# SparkFun_u-blox_GNSS_MAX-M10S.net
KiCad netlist of a schematic drawn in EAGLE
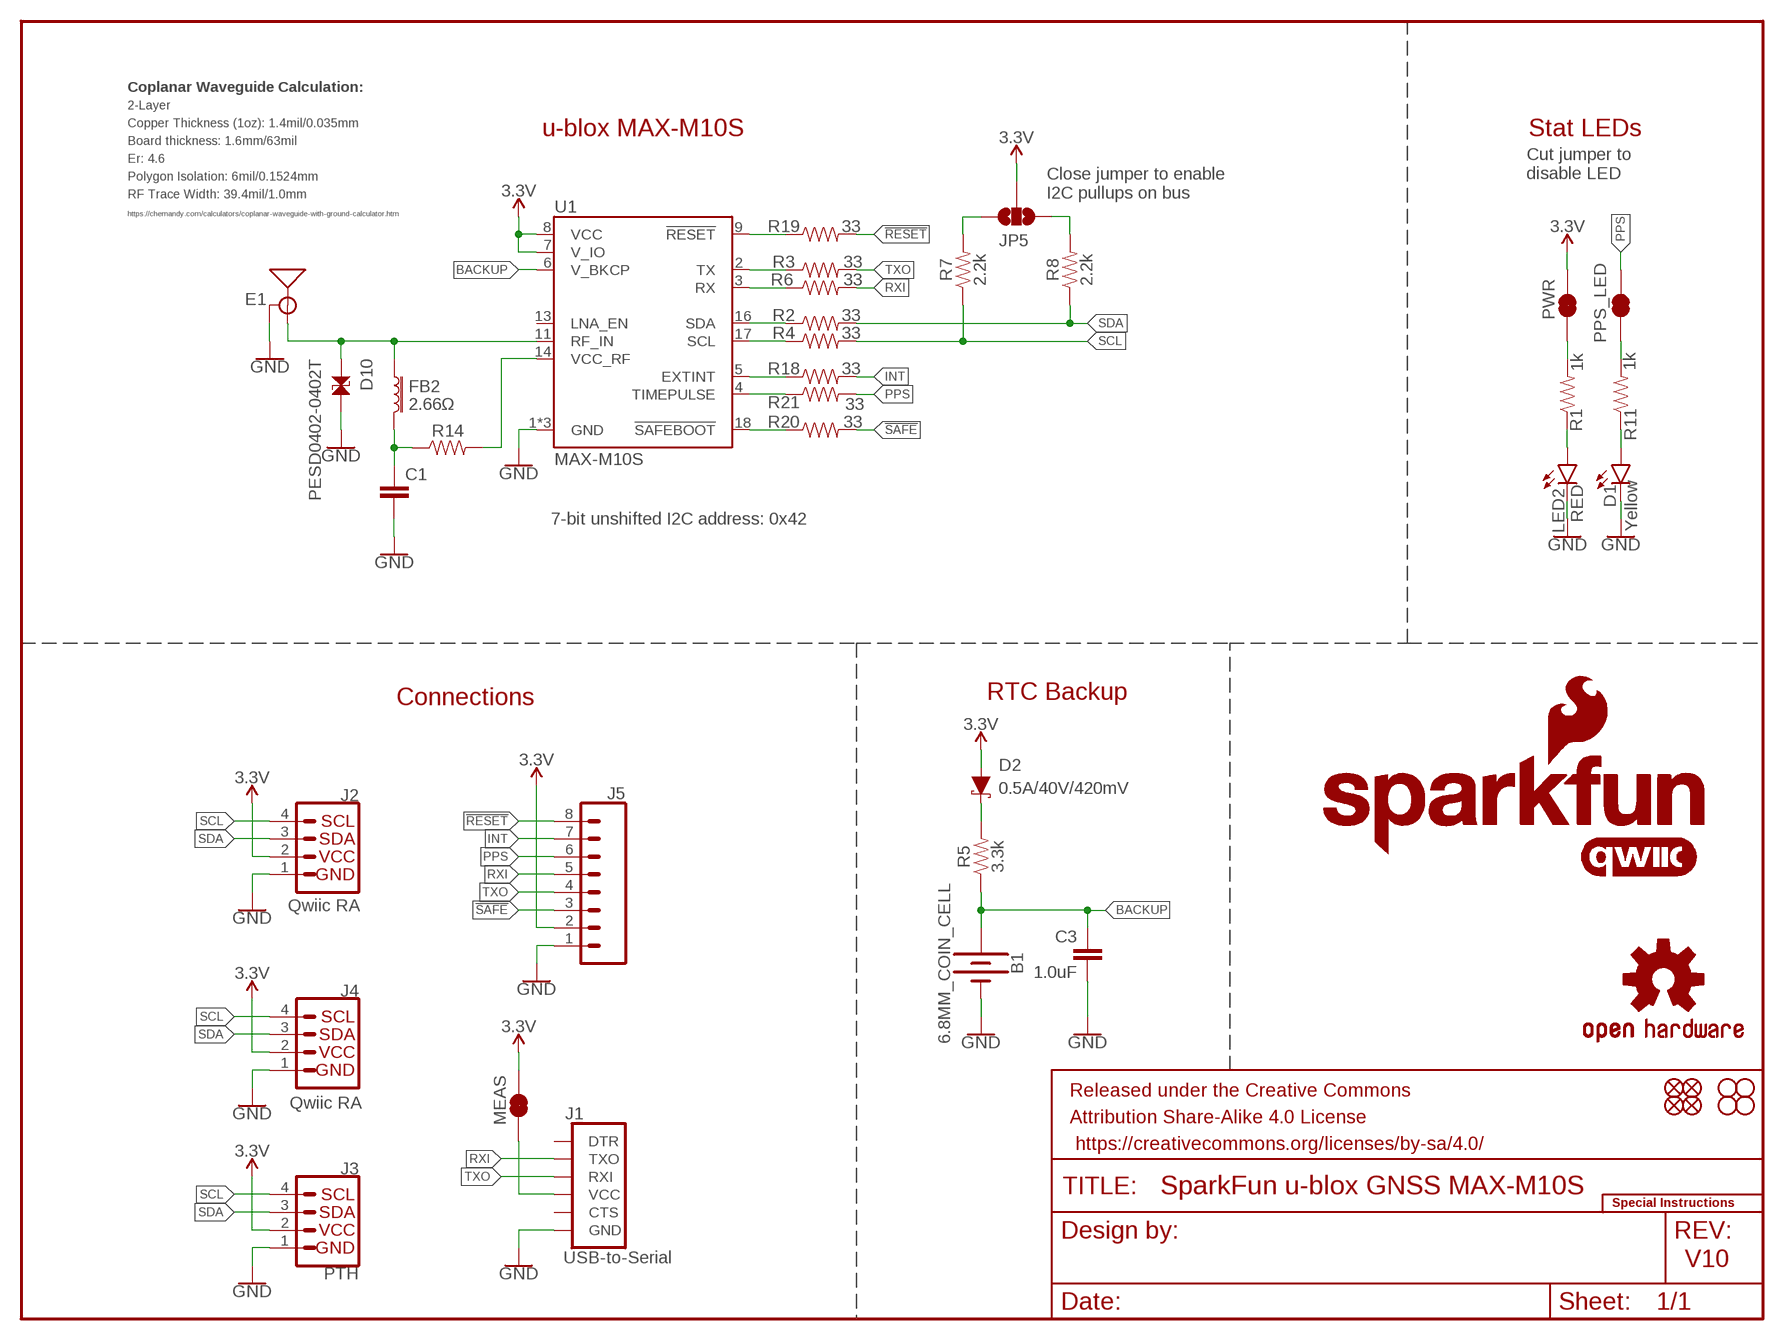
[diagram p0: schematic, sheet 1]

(export (version "E")
  (design (tool "Eeschema 10.0.6"))
  (components
    (comp (ref "B1")
      (value "6.8MM_COIN_CELL")
      (footprint "eagle-import:ML414H_IV01E")
      (libsource (lib "eagle-import") (part "ML414H_IV01E_BATTERY"))
    )
    (comp (ref "C1")
      (value "47pF")
      (footprint "eagle-import:0402-TIGHT")
      (libsource (lib "eagle-import") (part "47PF-0402_TIGHT-25V-5%-X7R"))
    )
    (comp (ref "C3")
      (value "1.0uF")
      (footprint "eagle-import:0603")
      (libsource (lib "eagle-import") (part "1.0UF-0603-16V-10%-X7R"))
    )
    (comp (ref "D1")
      (value "Yellow")
      (footprint "eagle-import:LED-0603")
      (libsource (lib "eagle-import") (part "LED-YELLOW0603"))
    )
    (comp (ref "D2")
      (value "0.5A/40V/420mV")
      (footprint "eagle-import:SOD-323")
      (libsource (lib "eagle-import") (part "DIODE-SCHOTTKY-PMEG4005EJ"))
    )
    (comp (ref "D10")
      (value "PESD0402-0402T")
      (footprint "eagle-import:0402-TIGHT")
      (libsource (lib "eagle-import") (part "PESD0402-0402T"))
    )
    (comp (ref "E1")
      (value "ANTENNA-SMA-GROUNDEDEDGE_SMA")
      (footprint "eagle-import:SMA-EDGE")
      (libsource (lib "eagle-import") (part "ANTENNA-SMA-GROUNDEDEDGE_SMA"))
    )
    (comp (ref "FB2")
      (value "2.66Ω")
      (footprint "eagle-import:0402-TIGHT")
      (libsource (lib "eagle-import") (part "FERRITE_BEAD-0402-2.66Ω-1GHZ"))
    )
    (comp (ref "FD1")
      (value "FIDUCIALUFIDUCIAL")
      (footprint "eagle-import:FIDUCIAL-MICRO")
      (libsource (lib "eagle-import") (part "FIDUCIALUFIDUCIAL"))
    )
    (comp (ref "FD2")
      (value "FIDUCIALUFIDUCIAL")
      (footprint "eagle-import:FIDUCIAL-MICRO")
      (libsource (lib "eagle-import") (part "FIDUCIALUFIDUCIAL"))
    )
    (comp (ref "FD3")
      (value "FIDUCIALUFIDUCIAL")
      (footprint "eagle-import:FIDUCIAL-MICRO")
      (libsource (lib "eagle-import") (part "FIDUCIALUFIDUCIAL"))
    )
    (comp (ref "FD4")
      (value "FIDUCIALUFIDUCIAL")
      (footprint "eagle-import:FIDUCIAL-MICRO")
      (libsource (lib "eagle-import") (part "FIDUCIALUFIDUCIAL"))
    )
    (comp (ref "FRAME1")
      (value "FRAME-LETTER")
      (footprint "eagle-import:CREATIVE_COMMONS")
      (libsource (lib "eagle-import") (part "FRAME-LETTER"))
    )
    (comp (ref "H1")
      (value "STAND-OFF")
      (footprint "eagle-import:STAND-OFF")
      (libsource (lib "eagle-import") (part "STAND-OFF"))
    )
    (comp (ref "H2")
      (value "STAND-OFF")
      (footprint "eagle-import:STAND-OFF")
      (libsource (lib "eagle-import") (part "STAND-OFF"))
    )
    (comp (ref "H3")
      (value "STAND-OFF")
      (footprint "eagle-import:STAND-OFF")
      (libsource (lib "eagle-import") (part "STAND-OFF"))
    )
    (comp (ref "H4")
      (value "STAND-OFF")
      (footprint "eagle-import:STAND-OFF")
      (libsource (lib "eagle-import") (part "STAND-OFF"))
    )
    (comp (ref "J1")
      (value "USB-to-Serial")
      (footprint "eagle-import:1X06_NO_SILK")
      (libsource (lib "eagle-import") (part "6_PIN_SERIAL_TARGET_NO_SILK"))
    )
    (comp (ref "J2")
      (value "Qwiic RA")
      (footprint "eagle-import:JST04_1MM_RA")
      (libsource (lib "eagle-import") (part "I2C_STANDARDQWIIC"))
    )
    (comp (ref "J3")
      (value "PTH")
      (footprint "eagle-import:1X04_NO_SILK")
      (libsource (lib "eagle-import") (part "SparkX_I2C_STANDARD_NO_SILK"))
    )
    (comp (ref "J4")
      (value "Qwiic RA")
      (footprint "eagle-import:JST04_1MM_RA")
      (libsource (lib "eagle-import") (part "I2C_STANDARDQWIIC"))
    )
    (comp (ref "J5")
      (value "CONN_08NO_SILK_DNP")
      (footprint "eagle-import:1X08_NO_SILK")
      (libsource (lib "eagle-import") (part "CONN_08NO_SILK_DNP"))
    )
    (comp (ref "JP5")
      (value "JUMPER-SMT_3_NO_SILK")
      (footprint "eagle-import:SMT-JUMPER_3_NO_SILK")
      (libsource (lib "eagle-import") (part "JUMPER-SMT_3_NO_SILK"))
    )
    (comp (ref "LED2")
      (value "RED")
      (footprint "eagle-import:LED-0603")
      (libsource (lib "eagle-import") (part "LED-RED0603"))
    )
    (comp (ref "LOGO1")
      (value "OSHW-LOGOMINI")
      (footprint "eagle-import:OSHW-LOGO-MINI")
      (libsource (lib "eagle-import") (part "OSHW-LOGOMINI"))
    )
    (comp (ref "LOGO2")
      (value "SFE_LOGO_NAME_FLAME.1_INCH")
      (footprint "eagle-import:SFE_LOGO_NAME_FLAME_.1")
      (libsource (lib "eagle-import") (part "SFE_LOGO_NAME_FLAME.1_INCH"))
    )
    (comp (ref "LOGO3")
      (value "QWIIC_LOGO_5MM")
      (footprint "eagle-import:QWIIC_5MM")
      (libsource (lib "eagle-import") (part "QWIIC_LOGO_5MM"))
    )
    (comp (ref "LOGO4")
      (value "SFE_LOGO_NAME.1_INCH")
      (footprint "eagle-import:SFE_LOGO_NAME_.1")
      (libsource (lib "eagle-import") (part "SFE_LOGO_NAME.1_INCH"))
    )
    (comp (ref "MEAS")
      (value "JUMPER-COMBO_2_NC_TRACE")
      (footprint "eagle-import:COMBO-JUMPER_2_NC_TRACE")
      (libsource (lib "eagle-import") (part "JUMPER-COMBO_2_NC_TRACE"))
    )
    (comp (ref "PPS_LED")
      (value "JUMPER-SMT_2_NC_TRACE_SILK")
      (footprint "eagle-import:SMT-JUMPER_2_NC_TRACE_SILK")
      (libsource (lib "eagle-import") (part "JUMPER-SMT_2_NC_TRACE_SILK"))
    )
    (comp (ref "PWR")
      (value "JUMPER-SMT_2_NC_TRACE_SILK")
      (footprint "eagle-import:SMT-JUMPER_2_NC_TRACE_SILK")
      (libsource (lib "eagle-import") (part "JUMPER-SMT_2_NC_TRACE_SILK"))
    )
    (comp (ref "R1")
      (value "1k")
      (footprint "eagle-import:0603")
      (libsource (lib "eagle-import") (part "1KOHM-0603-1/10W-1%"))
    )
    (comp (ref "R2")
      (value "33")
      (footprint "eagle-import:0603")
      (libsource (lib "eagle-import") (part "33OHM-0603-1/10W-1%"))
    )
    (comp (ref "R3")
      (value "33")
      (footprint "eagle-import:0603")
      (libsource (lib "eagle-import") (part "33OHM-0603-1/10W-1%"))
    )
    (comp (ref "R4")
      (value "33")
      (footprint "eagle-import:0603")
      (libsource (lib "eagle-import") (part "33OHM-0603-1/10W-1%"))
    )
    (comp (ref "R5")
      (value "3.3k")
      (footprint "eagle-import:0603")
      (libsource (lib "eagle-import") (part "3.3KOHM-0603-1/10W-1%"))
    )
    (comp (ref "R6")
      (value "33")
      (footprint "eagle-import:0603")
      (libsource (lib "eagle-import") (part "33OHM-0603-1/10W-1%"))
    )
    (comp (ref "R7")
      (value "2.2k")
      (footprint "eagle-import:0603")
      (libsource (lib "eagle-import") (part "2.2KOHM-0603-1/10W-1%"))
    )
    (comp (ref "R8")
      (value "2.2k")
      (footprint "eagle-import:0603")
      (libsource (lib "eagle-import") (part "2.2KOHM-0603-1/10W-1%"))
    )
    (comp (ref "R11")
      (value "1k")
      (footprint "eagle-import:0603")
      (libsource (lib "eagle-import") (part "1KOHM-0603-1/10W-1%"))
    )
    (comp (ref "R14")
      (value "33OHM-0402T-1/10W-1%")
      (footprint "eagle-import:0402-TIGHT")
      (libsource (lib "eagle-import") (part "33OHM-0402T-1/10W-1%"))
    )
    (comp (ref "R18")
      (value "33")
      (footprint "eagle-import:0603")
      (libsource (lib "eagle-import") (part "33OHM-0603-1/10W-1%"))
    )
    (comp (ref "R19")
      (value "33")
      (footprint "eagle-import:0603")
      (libsource (lib "eagle-import") (part "33OHM-0603-1/10W-1%"))
    )
    (comp (ref "R20")
      (value "33")
      (footprint "eagle-import:0603")
      (libsource (lib "eagle-import") (part "33OHM-0603-1/10W-1%"))
    )
    (comp (ref "R21")
      (value "33")
      (footprint "eagle-import:0603")
      (libsource (lib "eagle-import") (part "33OHM-0603-1/10W-1%"))
    )
    (comp (ref "U$2")
      (value "SPECIAL_INSTRUCTIONS-ORDERING")
      (footprint "eagle-import:ORDERING_INSTRUCTIONS")
      (libsource (lib "eagle-import") (part "SPECIAL_INSTRUCTIONS-ORDERING"))
    )
    (comp (ref "U1")
      (value "MAX-M10S")
      (footprint "eagle-import:MAX-M10S")
      (libsource (lib "eagle-import") (part "MAX-M10S"))
    )
  )
  (nets
    (net (code "1") (name "/~{RESET}") (class "Default")
      (node (ref "J5") (pin "8") (pinfunction "8_8") (pintype "passive"))
      (node (ref "R19") (pin "2") (pinfunction "2_2") (pintype "passive"))
    )
    (net (code "2") (name "/~{SAFE}") (class "Default")
      (node (ref "J5") (pin "3") (pinfunction "3_3") (pintype "passive"))
      (node (ref "R20") (pin "2") (pinfunction "2_2") (pintype "passive"))
    )
    (net (code "3") (name "3.3V") (class "Default")
      (node (ref "D2") (pin "A") (pinfunction "A_A") (pintype "passive"))
      (node (ref "J2") (pin "2") (pinfunction "2_2") (pintype "power_in"))
      (node (ref "J3") (pin "2") (pinfunction "VCC_2") (pintype "power_in"))
      (node (ref "J4") (pin "2") (pinfunction "2_2") (pintype "power_in"))
      (node (ref "J5") (pin "2") (pinfunction "2_2") (pintype "passive"))
      (node (ref "JP5") (pin "2") (pinfunction "2_2") (pintype "passive"))
      (node (ref "MEAS") (pin "2") (pinfunction "2_2") (pintype "passive"))
      (node (ref "MEAS") (pin "4") (pinfunction "2_4") (pintype "passive"))
      (node (ref "PWR") (pin "2") (pinfunction "2_2") (pintype "passive"))
      (node (ref "U1") (pin "7") (pinfunction "V_IO_7") (pintype "bidirectional"))
      (node (ref "U1") (pin "8") (pinfunction "VCC_8") (pintype "bidirectional"))
    )
    (net (code "4") (name "BACKUP") (class "Default")
      (node (ref "B1") (pin "+") (pinfunction "+_+") (pintype "power_in"))
      (node (ref "C3") (pin "1") (pinfunction "1_1") (pintype "passive"))
      (node (ref "R5") (pin "1") (pinfunction "1_1") (pintype "passive"))
      (node (ref "U1") (pin "6") (pinfunction "V_BKCP_6") (pintype "bidirectional"))
    )
    (net (code "5") (name "GND") (class "Default")
      (node (ref "B1") (pin "-") (pinfunction "-_-") (pintype "power_in"))
      (node (ref "C1") (pin "2") (pinfunction "2_2") (pintype "passive"))
      (node (ref "C3") (pin "2") (pinfunction "2_2") (pintype "passive"))
      (node (ref "D1") (pin "C") (pinfunction "C_C") (pintype "passive"))
      (node (ref "D10") (pin "2") (pinfunction "2_2") (pintype "bidirectional"))
      (node (ref "E1") (pin "GND@0") (pinfunction "GND_GND@0") (pintype "bidirectional"))
      (node (ref "E1") (pin "GND@1") (pinfunction "GND_GND@1") (pintype "bidirectional"))
      (node (ref "E1") (pin "GND@2") (pinfunction "GND_GND@2") (pintype "bidirectional"))
      (node (ref "E1") (pin "GND@3") (pinfunction "GND_GND@3") (pintype "bidirectional"))
      (node (ref "J1") (pin "6") (pinfunction "GND_6") (pintype "passive"))
      (node (ref "J2") (pin "1") (pinfunction "1_1") (pintype "power_in"))
      (node (ref "J3") (pin "1") (pinfunction "GND_1") (pintype "power_in"))
      (node (ref "J4") (pin "1") (pinfunction "1_1") (pintype "power_in"))
      (node (ref "J5") (pin "1") (pinfunction "1_1") (pintype "passive"))
      (node (ref "LED2") (pin "C") (pinfunction "C_C") (pintype "passive"))
      (node (ref "U1") (pin "1") (pinfunction "GND_1") (pintype "bidirectional"))
      (node (ref "U1") (pin "10") (pinfunction "GND_10") (pintype "bidirectional"))
      (node (ref "U1") (pin "12") (pinfunction "GND_12") (pintype "bidirectional"))
    )
    (net (code "6") (name "INT") (class "Default")
      (node (ref "J5") (pin "7") (pinfunction "7_7") (pintype "passive"))
      (node (ref "R18") (pin "2") (pinfunction "2_2") (pintype "passive"))
    )
    (net (code "7") (name "Net-(C1-Pad1)") (class "Default")
      (node (ref "C1") (pin "1") (pinfunction "1_1") (pintype "passive"))
      (node (ref "FB2") (pin "2") (pinfunction "2_2") (pintype "passive"))
      (node (ref "R14") (pin "1") (pinfunction "1_1") (pintype "passive"))
    )
    (net (code "8") (name "Net-(D1-PadA)") (class "Default")
      (node (ref "D1") (pin "A") (pinfunction "A_A") (pintype "passive"))
      (node (ref "R11") (pin "1") (pinfunction "1_1") (pintype "passive"))
    )
    (net (code "9") (name "Net-(D2-PadC)") (class "Default")
      (node (ref "D2") (pin "C") (pinfunction "C_C") (pintype "passive"))
      (node (ref "R5") (pin "2") (pinfunction "2_2") (pintype "passive"))
    )
    (net (code "10") (name "Net-(E1-SIGNAL)") (class "Default")
      (node (ref "D10") (pin "1") (pinfunction "1_1") (pintype "bidirectional"))
      (node (ref "E1") (pin "SIG") (pinfunction "SIGNAL_SIG") (pintype "bidirectional"))
      (node (ref "FB2") (pin "1") (pinfunction "1_1") (pintype "passive"))
      (node (ref "U1") (pin "11") (pinfunction "RF_IN_11") (pintype "bidirectional"))
    )
    (net (code "11") (name "Net-(J1-VCC)") (class "Default")
      (node (ref "J1") (pin "4") (pinfunction "VCC_4") (pintype "passive"))
      (node (ref "MEAS") (pin "1") (pinfunction "1_1") (pintype "passive"))
      (node (ref "MEAS") (pin "3") (pinfunction "1_3") (pintype "passive"))
    )
    (net (code "12") (name "Net-(JP5-Pad1)") (class "Default")
      (node (ref "JP5") (pin "1") (pinfunction "1_1") (pintype "passive"))
      (node (ref "R8") (pin "2") (pinfunction "2_2") (pintype "passive"))
    )
    (net (code "13") (name "Net-(JP5-Pad3)") (class "Default")
      (node (ref "JP5") (pin "3") (pinfunction "3_3") (pintype "passive"))
      (node (ref "R7") (pin "2") (pinfunction "2_2") (pintype "passive"))
    )
    (net (code "14") (name "Net-(LED2-PadA)") (class "Default")
      (node (ref "LED2") (pin "A") (pinfunction "A_A") (pintype "passive"))
      (node (ref "R1") (pin "1") (pinfunction "1_1") (pintype "passive"))
    )
    (net (code "15") (name "Net-(PPS_LED-Pad1)") (class "Default")
      (node (ref "PPS_LED") (pin "1") (pinfunction "1_1") (pintype "passive"))
      (node (ref "R11") (pin "2") (pinfunction "2_2") (pintype "passive"))
    )
    (net (code "16") (name "Net-(PWR-Pad1)") (class "Default")
      (node (ref "PWR") (pin "1") (pinfunction "1_1") (pintype "passive"))
      (node (ref "R1") (pin "2") (pinfunction "2_2") (pintype "passive"))
    )
    (net (code "17") (name "Net-(U1-EXTINT)") (class "Default")
      (node (ref "R18") (pin "1") (pinfunction "1_1") (pintype "passive"))
      (node (ref "U1") (pin "5") (pinfunction "EXTINT_5") (pintype "bidirectional"))
    )
    (net (code "18") (name "Net-(U1-RX)") (class "Default")
      (node (ref "R6") (pin "1") (pinfunction "1_1") (pintype "passive"))
      (node (ref "U1") (pin "3") (pinfunction "RX_3") (pintype "bidirectional"))
    )
    (net (code "19") (name "Net-(U1-SCL)") (class "Default")
      (node (ref "R4") (pin "1") (pinfunction "1_1") (pintype "passive"))
      (node (ref "U1") (pin "17") (pinfunction "SCL_17") (pintype "bidirectional"))
    )
    (net (code "20") (name "Net-(U1-SDA)") (class "Default")
      (node (ref "R2") (pin "1") (pinfunction "1_1") (pintype "passive"))
      (node (ref "U1") (pin "16") (pinfunction "SDA_16") (pintype "bidirectional"))
    )
    (net (code "21") (name "Net-(U1-TIMEPULSE)") (class "Default")
      (node (ref "R21") (pin "1") (pinfunction "1_1") (pintype "passive"))
      (node (ref "U1") (pin "4") (pinfunction "TIMEPULSE_4") (pintype "bidirectional"))
    )
    (net (code "22") (name "Net-(U1-TX)") (class "Default")
      (node (ref "R3") (pin "1") (pinfunction "1_1") (pintype "passive"))
      (node (ref "U1") (pin "2") (pinfunction "TX_2") (pintype "bidirectional"))
    )
    (net (code "23") (name "Net-(U1-VCC_RF)") (class "Default")
      (node (ref "R14") (pin "2") (pinfunction "2_2") (pintype "passive"))
      (node (ref "U1") (pin "14") (pinfunction "VCC_RF_14") (pintype "bidirectional"))
    )
    (net (code "24") (name "Net-(U1-~{RESET})") (class "Default")
      (node (ref "R19") (pin "1") (pinfunction "1_1") (pintype "passive"))
      (node (ref "U1") (pin "9") (pinfunction "~{RESET}_9") (pintype "bidirectional"))
    )
    (net (code "25") (name "Net-(U1-~{SAFEBOOT})") (class "Default")
      (node (ref "R20") (pin "1") (pinfunction "1_1") (pintype "passive"))
      (node (ref "U1") (pin "18") (pinfunction "~{SAFEBOOT}_18") (pintype "bidirectional"))
    )
    (net (code "26") (name "PPS") (class "Default")
      (node (ref "J5") (pin "6") (pinfunction "6_6") (pintype "passive"))
      (node (ref "PPS_LED") (pin "2") (pinfunction "2_2") (pintype "passive"))
      (node (ref "R21") (pin "2") (pinfunction "2_2") (pintype "passive"))
    )
    (net (code "27") (name "RXI") (class "Default")
      (node (ref "J1") (pin "3") (pinfunction "TXO_3") (pintype "passive"))
      (node (ref "J5") (pin "5") (pinfunction "5_5") (pintype "passive"))
      (node (ref "R6") (pin "2") (pinfunction "2_2") (pintype "passive"))
    )
    (net (code "28") (name "SCL") (class "Default")
      (node (ref "J2") (pin "4") (pinfunction "4_4") (pintype "passive"))
      (node (ref "J3") (pin "4") (pinfunction "SCL_4") (pintype "passive"))
      (node (ref "J4") (pin "4") (pinfunction "4_4") (pintype "passive"))
      (node (ref "R4") (pin "2") (pinfunction "2_2") (pintype "passive"))
      (node (ref "R7") (pin "1") (pinfunction "1_1") (pintype "passive"))
    )
    (net (code "29") (name "SDA") (class "Default")
      (node (ref "J2") (pin "3") (pinfunction "3_3") (pintype "passive"))
      (node (ref "J3") (pin "3") (pinfunction "SDA_3") (pintype "passive"))
      (node (ref "J4") (pin "3") (pinfunction "3_3") (pintype "passive"))
      (node (ref "R2") (pin "2") (pinfunction "2_2") (pintype "passive"))
      (node (ref "R8") (pin "1") (pinfunction "1_1") (pintype "passive"))
    )
    (net (code "30") (name "TXO") (class "Default")
      (node (ref "J1") (pin "2") (pinfunction "RXI_2") (pintype "passive"))
      (node (ref "J5") (pin "4") (pinfunction "4_4") (pintype "passive"))
      (node (ref "R3") (pin "2") (pinfunction "2_2") (pintype "passive"))
    )
    (net (code "31") (name "unconnected-(J1-CTS-Pad5)") (class "Default")
      (node (ref "J1") (pin "5") (pinfunction "CTS_5") (pintype "passive"))
    )
    (net (code "32") (name "unconnected-(J1-DTR-Pad1)") (class "Default")
      (node (ref "J1") (pin "1") (pinfunction "DTR_1") (pintype "passive"))
    )
    (net (code "33") (name "unconnected-(U1-LNA_EN-Pad13)") (class "Default")
      (node (ref "U1") (pin "13") (pinfunction "LNA_EN_13") (pintype "bidirectional"))
    )
  )
)
